# Domino_Single_USB.net
KiCad netlist of a schematic drawn in EAGLE
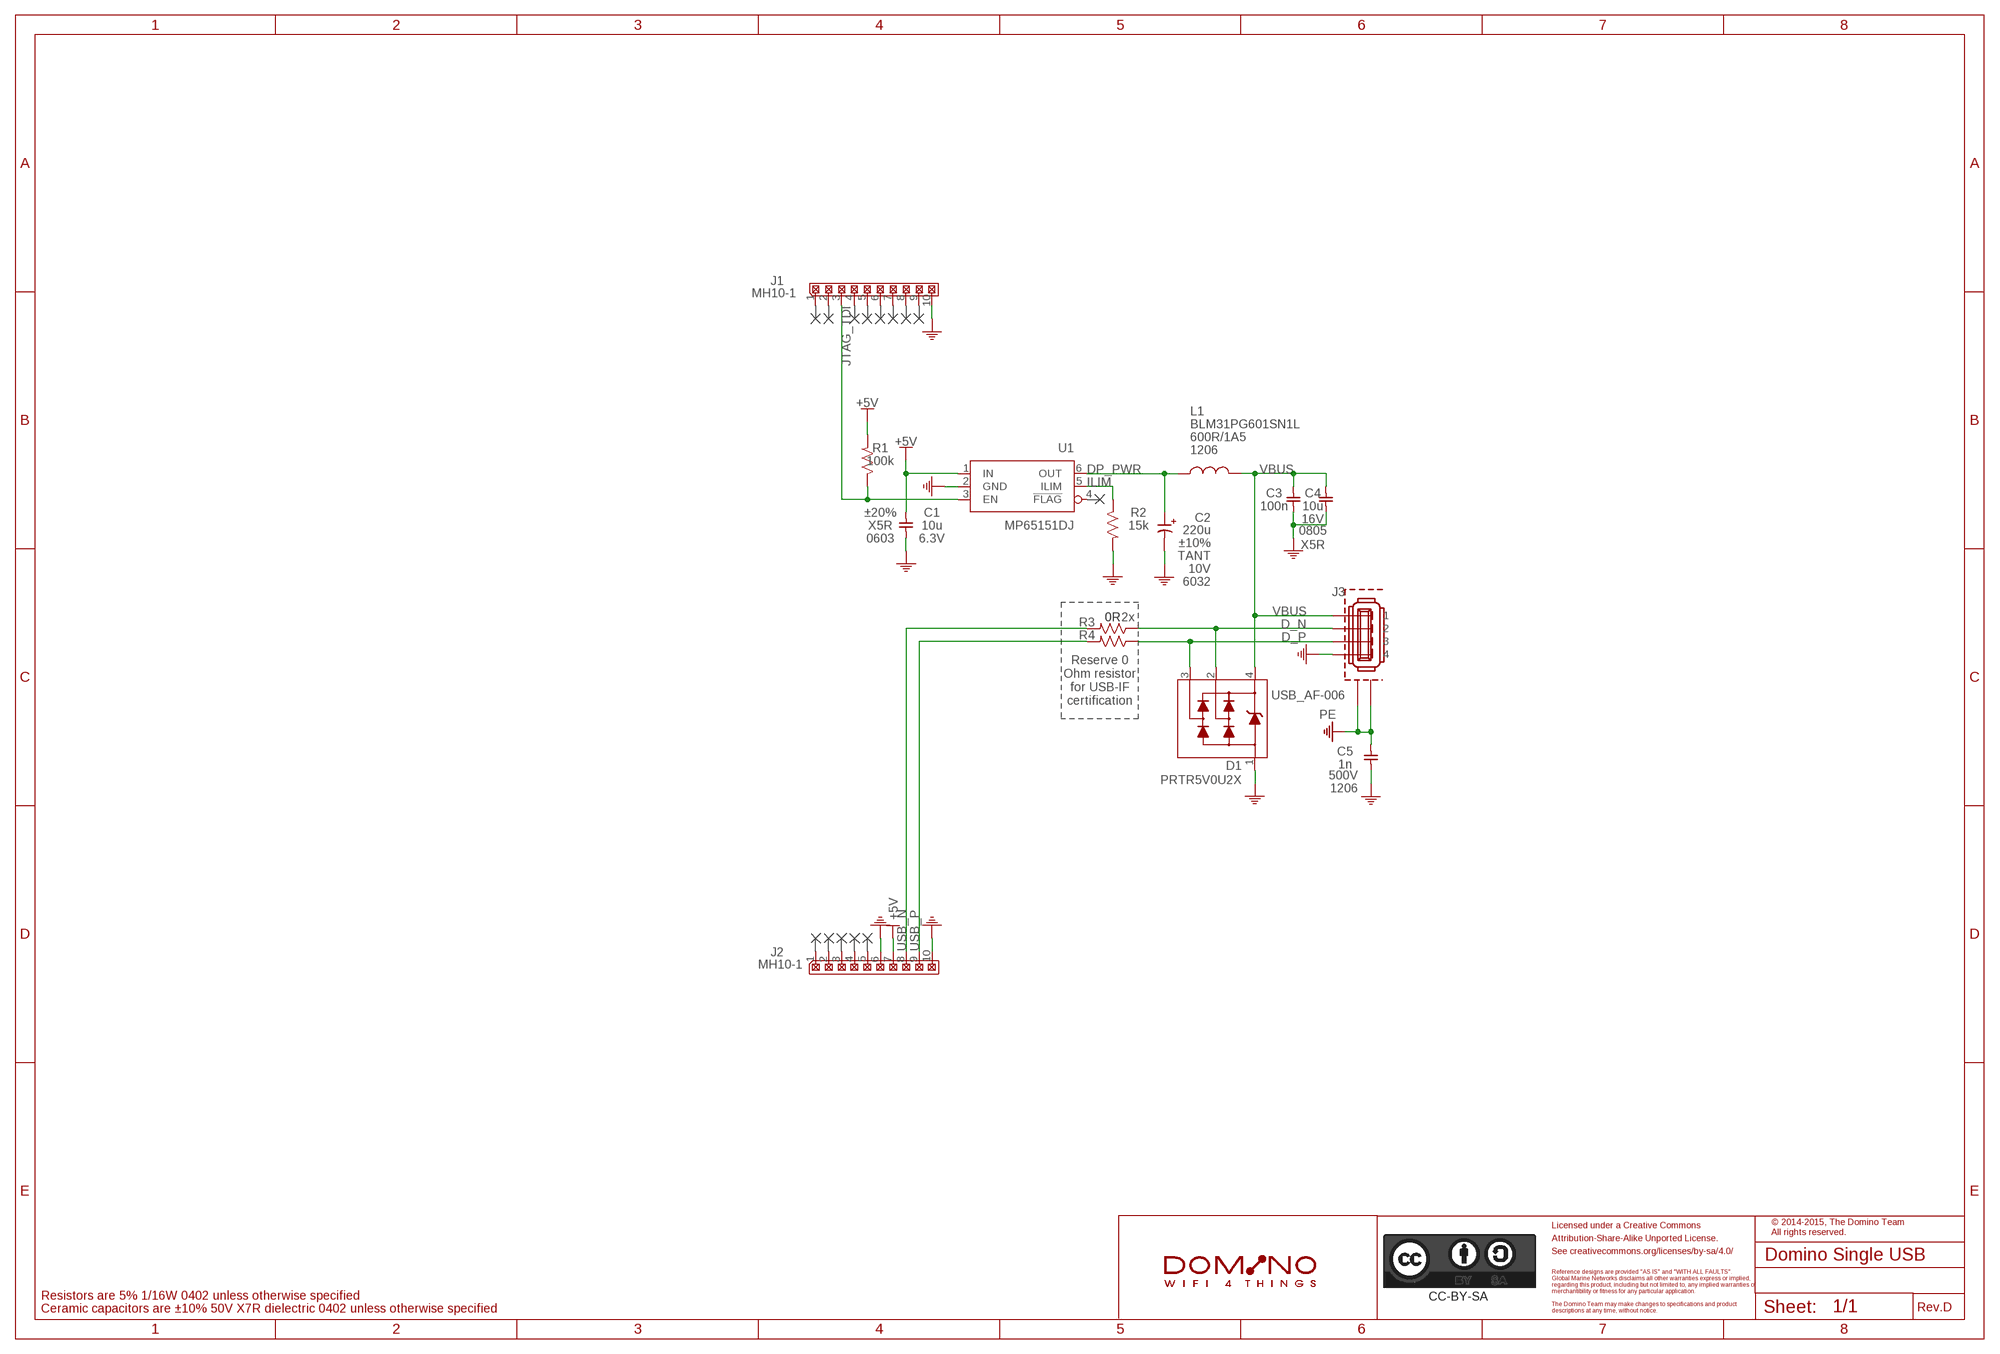
[diagram p0: schematic, sheet 1]

(export (version "E")
  (design (tool "Eeschema 10.0.6"))
  (components
    (comp (ref "C1")
      (value "10u")
      (footprint "eagle-import:C0603")
      (fields
        (field (name "SIZE") "0603")
        (field (name "PARTNO") "C0603_10u_X5R_20%_CER_6V3")
        (field (name "TC") "X5R")
        (field (name "TOL") "±20%")
        (field (name "VOLT") "6.3V")
      )
      (libsource (lib "eagle-import") (part "CAP_0603"))
    )
    (comp (ref "C2")
      (value "220u")
      (footprint "eagle-import:C_6032-25")
      (fields
        (field (name "SIZE") "6032")
        (field (name "TYPE") "TANT")
        (field (name "PARTNO") "CPOLC-6032_220u_20%_TANT_10V")
        (field (name "TOL") "±10%")
        (field (name "VOLT") "10V")
      )
      (libsource (lib "eagle-import") (part "CPOL_?C/6032-25"))
    )
    (comp (ref "C3")
      (value "100n")
      (footprint "eagle-import:C0402")
      (fields (field (name "PARTNO") "C0402_100n_X7R_10%_CER_50V"))
      (libsource (lib "eagle-import") (part "CAP_0402"))
    )
    (comp (ref "C4")
      (value "10u")
      (footprint "eagle-import:C0805")
      (fields
        (field (name "SIZE") "0805")
        (field (name "PARTNO") "C0805_10u_X5R_10%_CER_16V")
        (field (name "TC") "X5R")
        (field (name "VOLT") "16V")
      )
      (libsource (lib "eagle-import") (part "CAP_0805"))
    )
    (comp (ref "C5")
      (value "1n")
      (footprint "eagle-import:C1206")
      (fields
        (field (name "SIZE") "1206")
        (field (name "PARTNO") "C1206_1n_X7R_10%_CER_500V")
        (field (name "VOLT") "500V")
      )
      (libsource (lib "eagle-import") (part "CAP_1206"))
    )
    (comp (ref "CC-BY-SA1")
      (value "CC-BY-SA_LOGO")
      (footprint "eagle-import:CC-BY-SA_LOGO")
      (libsource (lib "eagle-import") (part "CC-BY-SA_LOGO"))
    )
    (comp (ref "D1")
      (value "PRTR5V0U2X")
      (footprint "eagle-import:SOT143B")
      (libsource (lib "eagle-import") (part "PRTR5V0U2X"))
    )
    (comp (ref "J1")
      (value "MH10-1")
      (footprint "eagle-import:MH10-1-0.1")
      (fields (field (name "PARTNO") "MH10-1-0.1"))
      (libsource (lib "eagle-import") (part "MH10-1"))
    )
    (comp (ref "J2")
      (value "MH10-1")
      (footprint "eagle-import:MH10-1-0.1")
      (fields (field (name "PARTNO") "MH10-1-0.1"))
      (libsource (lib "eagle-import") (part "MH10-1"))
    )
    (comp (ref "J3")
      (value "USB_AF-006")
      (footprint "eagle-import:USB_AF-006")
      (libsource (lib "eagle-import") (part "USB_AF-006"))
    )
    (comp (ref "L1")
      (value "BLM31PG601SN1L")
      (footprint "eagle-import:FB1206")
      (fields (field (name "SIZE") "1206") (field (name "OPT") "600R/1A5"))
      (libsource (lib "eagle-import") (part "FB_1206"))
    )
    (comp (ref "R1")
      (value "100k")
      (footprint "eagle-import:R0402")
      (fields (field (name "PARTNO") "R0402_100k_5%_62.5mW"))
      (libsource (lib "eagle-import") (part "RES_0402"))
    )
    (comp (ref "R2")
      (value "15k")
      (footprint "eagle-import:R0402")
      (fields (field (name "PARTNO") "R0402_15k_5%_62.5mW"))
      (libsource (lib "eagle-import") (part "RES_0402"))
    )
    (comp (ref "R3")
      (value "0R")
      (footprint "eagle-import:R0402")
      (fields (field (name "PARTNO") "R0402_0R_5%_62.5mW"))
      (libsource (lib "eagle-import") (part "RES_0402"))
    )
    (comp (ref "R4")
      (value "0R")
      (footprint "eagle-import:R0402")
      (fields (field (name "PARTNO") "R0402_0R_5%_62.5mW"))
      (libsource (lib "eagle-import") (part "RES_0402"))
    )
    (comp (ref "S1")
      (value "DOMINO_LOGO")
      (footprint "eagle-import:DOMINO_LOGO")
      (libsource (lib "eagle-import") (part "DOMINO_LOGO"))
    )
    (comp (ref "U1")
      (value "MP65151DJ")
      (footprint "eagle-import:SOT23-6")
      (libsource (lib "eagle-import") (part "MP65151DJ"))
    )
  )
  (nets
    (net (code "1") (name "+5V") (class "Default")
      (node (ref "C1") (pin "1") (pinfunction "1_1") (pintype "passive"))
      (node (ref "J2") (pin "7") (pinfunction "7_7") (pintype "passive"))
      (node (ref "R1") (pin "2") (pinfunction "2_2") (pintype "passive"))
      (node (ref "U1") (pin "1") (pinfunction "IN_1") (pintype "power_in"))
    )
    (net (code "2") (name "/DP_PWR") (class "Default")
      (node (ref "C2") (pin "1") (pinfunction "+_1") (pintype "passive"))
      (node (ref "L1") (pin "1") (pinfunction "1_1") (pintype "passive"))
      (node (ref "U1") (pin "6") (pinfunction "OUT_6") (pintype "power_in"))
    )
    (net (code "3") (name "/D_N") (class "Default")
      (node (ref "D1") (pin "2") (pinfunction "P$2_2") (pintype "passive"))
      (node (ref "J3") (pin "2") (pinfunction "2_2") (pintype "passive"))
      (node (ref "R3") (pin "1") (pinfunction "1_1") (pintype "passive"))
    )
    (net (code "4") (name "/D_P") (class "Default")
      (node (ref "D1") (pin "3") (pinfunction "P$3_3") (pintype "passive"))
      (node (ref "J3") (pin "3") (pinfunction "3_3") (pintype "passive"))
      (node (ref "R4") (pin "1") (pinfunction "1_1") (pintype "passive"))
    )
    (net (code "5") (name "/ILIM") (class "Default")
      (node (ref "R2") (pin "1") (pinfunction "1_1") (pintype "passive"))
      (node (ref "U1") (pin "5") (pinfunction "ILIM_5") (pintype "passive"))
    )
    (net (code "6") (name "/JTAG_TDI") (class "Default")
      (node (ref "J1") (pin "3") (pinfunction "3_3") (pintype "passive"))
      (node (ref "R1") (pin "1") (pinfunction "1_1") (pintype "passive"))
      (node (ref "U1") (pin "3") (pinfunction "EN_3") (pintype "input"))
    )
    (net (code "7") (name "/USB_N") (class "Default")
      (node (ref "J2") (pin "8") (pinfunction "8_8") (pintype "passive"))
      (node (ref "R3") (pin "2") (pinfunction "2_2") (pintype "passive"))
    )
    (net (code "8") (name "/USB_P") (class "Default")
      (node (ref "J2") (pin "9") (pinfunction "9_9") (pintype "passive"))
      (node (ref "R4") (pin "2") (pinfunction "2_2") (pintype "passive"))
    )
    (net (code "9") (name "/VBUS") (class "Default")
      (node (ref "C3") (pin "1") (pinfunction "1_1") (pintype "passive"))
      (node (ref "C4") (pin "1") (pinfunction "1_1") (pintype "passive"))
      (node (ref "D1") (pin "4") (pinfunction "P$4_4") (pintype "passive"))
      (node (ref "J3") (pin "1") (pinfunction "1_1") (pintype "passive"))
      (node (ref "L1") (pin "2") (pinfunction "2_2") (pintype "passive"))
    )
    (net (code "10") (name "GND") (class "Default")
      (node (ref "C1") (pin "2") (pinfunction "2_2") (pintype "passive"))
      (node (ref "C2") (pin "2") (pinfunction "-_2") (pintype "passive"))
      (node (ref "C3") (pin "2") (pinfunction "2_2") (pintype "passive"))
      (node (ref "C4") (pin "2") (pinfunction "2_2") (pintype "passive"))
      (node (ref "C5") (pin "2") (pinfunction "2_2") (pintype "passive"))
      (node (ref "D1") (pin "1") (pinfunction "P$1_1") (pintype "passive"))
      (node (ref "J1") (pin "10") (pinfunction "10_10") (pintype "passive"))
      (node (ref "J2") (pin "10") (pinfunction "10_10") (pintype "passive"))
      (node (ref "J2") (pin "6") (pinfunction "6_6") (pintype "passive"))
      (node (ref "J3") (pin "4") (pinfunction "4_4") (pintype "passive"))
      (node (ref "R2") (pin "2") (pinfunction "2_2") (pintype "passive"))
      (node (ref "U1") (pin "2") (pinfunction "GND_2") (pintype "power_in"))
    )
    (net (code "11") (name "PE") (class "Default")
      (node (ref "C5") (pin "1") (pinfunction "1_1") (pintype "passive"))
      (node (ref "J3") (pin "S$1") (pinfunction "G_S$1") (pintype "passive"))
      (node (ref "J3") (pin "S$2") (pinfunction "G_S$2") (pintype "passive"))
    )
    (net (code "12") (name "unconnected-(J1-Pad1)") (class "Default")
      (node (ref "J1") (pin "1") (pinfunction "1_1") (pintype "passive"))
    )
    (net (code "13") (name "unconnected-(J1-Pad2)") (class "Default")
      (node (ref "J1") (pin "2") (pinfunction "2_2") (pintype "passive"))
    )
    (net (code "14") (name "unconnected-(J1-Pad4)") (class "Default")
      (node (ref "J1") (pin "4") (pinfunction "4_4") (pintype "passive"))
    )
    (net (code "15") (name "unconnected-(J1-Pad5)") (class "Default")
      (node (ref "J1") (pin "5") (pinfunction "5_5") (pintype "passive"))
    )
    (net (code "16") (name "unconnected-(J1-Pad6)") (class "Default")
      (node (ref "J1") (pin "6") (pinfunction "6_6") (pintype "passive"))
    )
    (net (code "17") (name "unconnected-(J1-Pad7)") (class "Default")
      (node (ref "J1") (pin "7") (pinfunction "7_7") (pintype "passive"))
    )
    (net (code "18") (name "unconnected-(J1-Pad8)") (class "Default")
      (node (ref "J1") (pin "8") (pinfunction "8_8") (pintype "passive"))
    )
    (net (code "19") (name "unconnected-(J1-Pad9)") (class "Default")
      (node (ref "J1") (pin "9") (pinfunction "9_9") (pintype "passive"))
    )
    (net (code "20") (name "unconnected-(J2-Pad1)") (class "Default")
      (node (ref "J2") (pin "1") (pinfunction "1_1") (pintype "passive"))
    )
    (net (code "21") (name "unconnected-(J2-Pad2)") (class "Default")
      (node (ref "J2") (pin "2") (pinfunction "2_2") (pintype "passive"))
    )
    (net (code "22") (name "unconnected-(J2-Pad3)") (class "Default")
      (node (ref "J2") (pin "3") (pinfunction "3_3") (pintype "passive"))
    )
    (net (code "23") (name "unconnected-(J2-Pad4)") (class "Default")
      (node (ref "J2") (pin "4") (pinfunction "4_4") (pintype "passive"))
    )
    (net (code "24") (name "unconnected-(J2-Pad5)") (class "Default")
      (node (ref "J2") (pin "5") (pinfunction "5_5") (pintype "passive"))
    )
    (net (code "25") (name "unconnected-(U1-~{FLAG}-Pad4)") (class "Default")
      (node (ref "U1") (pin "4") (pinfunction "~{FLAG}_4") (pintype "open_collector"))
    )
  )
)
